# ExtensionConnector.net
KiCad netlist of a schematic drawn in Altium Designer
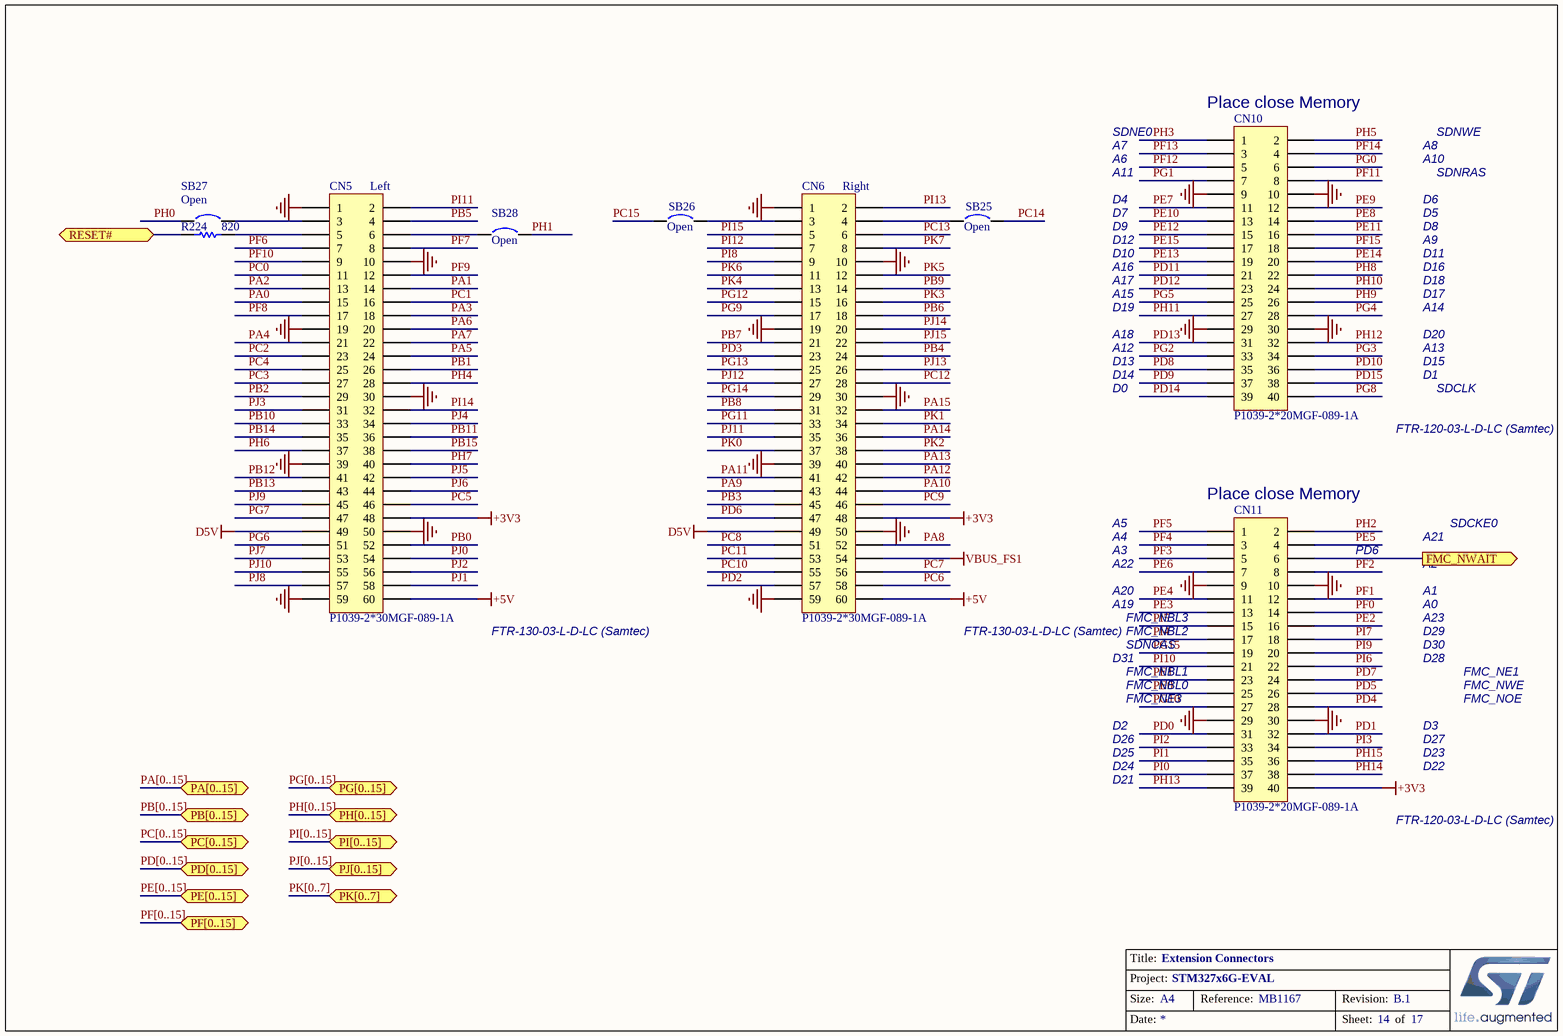
[diagram p0: ExtensionConnector.SchDoc]

(export (version "E")
  (design (tool "Eeschema 10.0.6"))
  (components
    (comp (ref "CN5")
      (value "P1039-2*30MGF-089-1A")
      (footprint "FTR-130-53-L-D-LC")
      (description "Header, 40-Pin, Dual row")
      (fields (field (name "PUBLISHER") "Altium Limited"))
      (libsource (lib "mb1045") (part "FTR-130-53-L-D-LC"))
    )
    (comp (ref "CN6")
      (value "P1039-2*30MGF-089-1A")
      (footprint "FTR-130-53-L-D-LC")
      (description "Header, 40-Pin, Dual row")
      (fields (field (name "PUBLISHER") "Altium Limited"))
      (libsource (lib "mb1045") (part "FTR-130-53-L-D-LC"))
    )
    (comp (ref "CN10")
      (value "P1039-2*20MGF-089-1A")
      (footprint "FTR-120-53-L-D-LC")
      (description "Header, 20-Pin, Dual row")
      (fields (field (name "PUBLISHER") "Altium Limited"))
      (libsource (lib "mb1045") (part "FTR-120-53-L-D-LC"))
    )
    (comp (ref "CN11")
      (value "P1039-2*20MGF-089-1A")
      (footprint "FTR-120-53-L-D-LC")
      (description "Header, 20-Pin, Dual row")
      (fields (field (name "PUBLISHER") "Altium Limited"))
      (libsource (lib "mb1045") (part "FTR-120-53-L-D-LC"))
    )
    (comp (ref "R224")
      (value "820")
      (footprint "0603R")
      (description "Resistor")
      (fields (field (name "PUBLISHER") "Altium Limited"))
      (libsource (lib "Miscellaneous Devices") (part "res1"))
    )
    (comp (ref "SB25")
      (value "Open")
      (footprint "SB_0603")
      (description "Circuit Breaker")
      (fields (field (name "PUBLISHER") "Altium Limited"))
      (libsource (lib "MB1167") (part "Circuit Breaker"))
    )
    (comp (ref "SB26")
      (value "Open")
      (footprint "SB_0603")
      (description "Circuit Breaker")
      (fields (field (name "PUBLISHER") "Altium Limited"))
      (libsource (lib "") (part "Circuit Breaker_1"))
    )
    (comp (ref "SB27")
      (value "Open")
      (footprint "SB_0603")
      (description "Circuit Breaker")
      (fields (field (name "PUBLISHER") "Altium Limited"))
      (libsource (lib "") (part "Circuit Breaker_1"))
    )
    (comp (ref "SB28")
      (value "Open")
      (footprint "SB_0603")
      (description "Circuit Breaker")
      (fields (field (name "PUBLISHER") "Altium Limited"))
      (libsource (lib "MB1167") (part "Circuit Breaker"))
    )
  )
  (nets
    (net (code "1") (name "+3V3") (class "Default")
      (node (ref "CN11") (pin "40") (pinfunction "40_40") (pintype "passive"))
      (node (ref "CN5") (pin "48") (pinfunction "48_48") (pintype "passive"))
      (node (ref "CN6") (pin "48") (pinfunction "48_48") (pintype "passive"))
    )
    (net (code "2") (name "+5V") (class "Default")
      (node (ref "CN5") (pin "60") (pinfunction "60_60") (pintype "passive"))
      (node (ref "CN6") (pin "60") (pinfunction "60_60") (pintype "passive"))
    )
    (net (code "3") (name "/FMC_NWAIT") (class "Default")
      (node (ref "CN11") (pin "6") (pinfunction "6_6") (pintype "passive"))
    )
    (net (code "4") (name "/PA0") (class "Default")
      (node (ref "CN5") (pin "15") (pinfunction "15_15") (pintype "passive"))
    )
    (net (code "5") (name "/PA1") (class "Default")
      (node (ref "CN5") (pin "14") (pinfunction "14_14") (pintype "passive"))
    )
    (net (code "6") (name "/PA2") (class "Default")
      (node (ref "CN5") (pin "13") (pinfunction "13_13") (pintype "passive"))
    )
    (net (code "7") (name "/PA3") (class "Default")
      (node (ref "CN5") (pin "18") (pinfunction "18_18") (pintype "passive"))
    )
    (net (code "8") (name "/PA4") (class "Default")
      (node (ref "CN5") (pin "21") (pinfunction "21_21") (pintype "passive"))
    )
    (net (code "9") (name "/PA5") (class "Default")
      (node (ref "CN5") (pin "24") (pinfunction "24_24") (pintype "passive"))
    )
    (net (code "10") (name "/PA6") (class "Default")
      (node (ref "CN5") (pin "20") (pinfunction "20_20") (pintype "passive"))
    )
    (net (code "11") (name "/PA7") (class "Default")
      (node (ref "CN5") (pin "22") (pinfunction "22_22") (pintype "passive"))
    )
    (net (code "12") (name "/PA8") (class "Default")
      (node (ref "CN6") (pin "52") (pinfunction "52_52") (pintype "passive"))
    )
    (net (code "13") (name "/PA9") (class "Default")
      (node (ref "CN6") (pin "43") (pinfunction "43_43") (pintype "passive"))
    )
    (net (code "14") (name "/PA10") (class "Default")
      (node (ref "CN6") (pin "44") (pinfunction "44_44") (pintype "passive"))
    )
    (net (code "15") (name "/PA11") (class "Default")
      (node (ref "CN6") (pin "41") (pinfunction "41_41") (pintype "passive"))
    )
    (net (code "16") (name "/PA12") (class "Default")
      (node (ref "CN6") (pin "42") (pinfunction "42_42") (pintype "passive"))
    )
    (net (code "17") (name "/PA13") (class "Default")
      (node (ref "CN6") (pin "40") (pinfunction "40_40") (pintype "passive"))
    )
    (net (code "18") (name "/PA14") (class "Default")
      (node (ref "CN6") (pin "36") (pinfunction "36_36") (pintype "passive"))
    )
    (net (code "19") (name "/PA15") (class "Default")
      (node (ref "CN6") (pin "32") (pinfunction "32_32") (pintype "passive"))
    )
    (net (code "21") (name "/PB0") (class "Default")
      (node (ref "CN5") (pin "52") (pinfunction "52_52") (pintype "passive"))
    )
    (net (code "22") (name "/PB1") (class "Default")
      (node (ref "CN5") (pin "26") (pinfunction "26_26") (pintype "passive"))
    )
    (net (code "23") (name "/PB2") (class "Default")
      (node (ref "CN5") (pin "29") (pinfunction "29_29") (pintype "passive"))
    )
    (net (code "24") (name "/PB3") (class "Default")
      (node (ref "CN6") (pin "45") (pinfunction "45_45") (pintype "passive"))
    )
    (net (code "25") (name "/PB4") (class "Default")
      (node (ref "CN6") (pin "24") (pinfunction "24_24") (pintype "passive"))
    )
    (net (code "26") (name "/PB5") (class "Default")
      (node (ref "CN5") (pin "4") (pinfunction "4_4") (pintype "passive"))
    )
    (net (code "27") (name "/PB6") (class "Default")
      (node (ref "CN6") (pin "18") (pinfunction "18_18") (pintype "passive"))
    )
    (net (code "28") (name "/PB7") (class "Default")
      (node (ref "CN6") (pin "21") (pinfunction "21_21") (pintype "passive"))
    )
    (net (code "29") (name "/PB8") (class "Default")
      (node (ref "CN6") (pin "31") (pinfunction "31_31") (pintype "passive"))
    )
    (net (code "30") (name "/PB9") (class "Default")
      (node (ref "CN6") (pin "14") (pinfunction "14_14") (pintype "passive"))
    )
    (net (code "31") (name "/PB10") (class "Default")
      (node (ref "CN5") (pin "33") (pinfunction "33_33") (pintype "passive"))
    )
    (net (code "32") (name "/PB11") (class "Default")
      (node (ref "CN5") (pin "36") (pinfunction "36_36") (pintype "passive"))
    )
    (net (code "33") (name "/PB12") (class "Default")
      (node (ref "CN5") (pin "41") (pinfunction "41_41") (pintype "passive"))
    )
    (net (code "34") (name "/PB13") (class "Default")
      (node (ref "CN5") (pin "43") (pinfunction "43_43") (pintype "passive"))
    )
    (net (code "35") (name "/PB14") (class "Default")
      (node (ref "CN5") (pin "35") (pinfunction "35_35") (pintype "passive"))
    )
    (net (code "36") (name "/PB15") (class "Default")
      (node (ref "CN5") (pin "38") (pinfunction "38_38") (pintype "passive"))
    )
    (net (code "38") (name "/PC0") (class "Default")
      (node (ref "CN5") (pin "11") (pinfunction "11_11") (pintype "passive"))
    )
    (net (code "39") (name "/PC1") (class "Default")
      (node (ref "CN5") (pin "16") (pinfunction "16_16") (pintype "passive"))
    )
    (net (code "40") (name "/PC2") (class "Default")
      (node (ref "CN5") (pin "23") (pinfunction "23_23") (pintype "passive"))
    )
    (net (code "41") (name "/PC3") (class "Default")
      (node (ref "CN5") (pin "27") (pinfunction "27_27") (pintype "passive"))
    )
    (net (code "42") (name "/PC4") (class "Default")
      (node (ref "CN5") (pin "25") (pinfunction "25_25") (pintype "passive"))
    )
    (net (code "43") (name "/PC5") (class "Default")
      (node (ref "CN5") (pin "46") (pinfunction "46_46") (pintype "passive"))
    )
    (net (code "44") (name "/PC6") (class "Default")
      (node (ref "CN6") (pin "58") (pinfunction "58_58") (pintype "passive"))
    )
    (net (code "45") (name "/PC7") (class "Default")
      (node (ref "CN6") (pin "56") (pinfunction "56_56") (pintype "passive"))
    )
    (net (code "46") (name "/PC8") (class "Default")
      (node (ref "CN6") (pin "51") (pinfunction "51_51") (pintype "passive"))
    )
    (net (code "47") (name "/PC9") (class "Default")
      (node (ref "CN6") (pin "46") (pinfunction "46_46") (pintype "passive"))
    )
    (net (code "48") (name "/PC10") (class "Default")
      (node (ref "CN6") (pin "55") (pinfunction "55_55") (pintype "passive"))
    )
    (net (code "49") (name "/PC11") (class "Default")
      (node (ref "CN6") (pin "53") (pinfunction "53_53") (pintype "passive"))
    )
    (net (code "50") (name "/PC12") (class "Default")
      (node (ref "CN6") (pin "28") (pinfunction "28_28") (pintype "passive"))
    )
    (net (code "51") (name "/PC13") (class "Default")
      (node (ref "CN6") (pin "6") (pinfunction "6_6") (pintype "passive"))
    )
    (net (code "52") (name "/PC14") (class "Default")
      (node (ref "SB25") (pin "1") (pinfunction "1_1") (pintype "passive"))
    )
    (net (code "53") (name "/PC15") (class "Default")
      (node (ref "SB26") (pin "1") (pinfunction "1_1") (pintype "passive"))
    )
    (net (code "55") (name "/PD0") (class "Default")
      (node (ref "CN11") (pin "31") (pinfunction "31_31") (pintype "passive"))
    )
    (net (code "56") (name "/PD1") (class "Default")
      (node (ref "CN11") (pin "32") (pinfunction "32_32") (pintype "passive"))
    )
    (net (code "57") (name "/PD2") (class "Default")
      (node (ref "CN6") (pin "57") (pinfunction "57_57") (pintype "passive"))
    )
    (net (code "58") (name "/PD3") (class "Default")
      (node (ref "CN6") (pin "23") (pinfunction "23_23") (pintype "passive"))
    )
    (net (code "59") (name "/PD4") (class "Default")
      (node (ref "CN11") (pin "28") (pinfunction "28_28") (pintype "passive"))
    )
    (net (code "60") (name "/PD5") (class "Default")
      (node (ref "CN11") (pin "26") (pinfunction "26_26") (pintype "passive"))
    )
    (net (code "61") (name "/PD6") (class "Default")
      (node (ref "CN6") (pin "47") (pinfunction "47_47") (pintype "passive"))
    )
    (net (code "62") (name "/PD7") (class "Default")
      (node (ref "CN11") (pin "24") (pinfunction "24_24") (pintype "passive"))
    )
    (net (code "63") (name "/PD8") (class "Default")
      (node (ref "CN10") (pin "35") (pinfunction "35_35") (pintype "passive"))
    )
    (net (code "64") (name "/PD9") (class "Default")
      (node (ref "CN10") (pin "37") (pinfunction "37_37") (pintype "passive"))
    )
    (net (code "65") (name "/PD10") (class "Default")
      (node (ref "CN10") (pin "36") (pinfunction "36_36") (pintype "passive"))
    )
    (net (code "66") (name "/PD11") (class "Default")
      (node (ref "CN10") (pin "21") (pinfunction "21_21") (pintype "passive"))
    )
    (net (code "67") (name "/PD12") (class "Default")
      (node (ref "CN10") (pin "23") (pinfunction "23_23") (pintype "passive"))
    )
    (net (code "68") (name "/PD13") (class "Default")
      (node (ref "CN10") (pin "31") (pinfunction "31_31") (pintype "passive"))
    )
    (net (code "69") (name "/PD14") (class "Default")
      (node (ref "CN10") (pin "39") (pinfunction "39_39") (pintype "passive"))
    )
    (net (code "70") (name "/PD15") (class "Default")
      (node (ref "CN10") (pin "38") (pinfunction "38_38") (pintype "passive"))
    )
    (net (code "72") (name "/PE0") (class "Default")
      (node (ref "CN11") (pin "25") (pinfunction "25_25") (pintype "passive"))
    )
    (net (code "73") (name "/PE1") (class "Default")
      (node (ref "CN11") (pin "23") (pinfunction "23_23") (pintype "passive"))
    )
    (net (code "74") (name "/PE2") (class "Default")
      (node (ref "CN11") (pin "16") (pinfunction "16_16") (pintype "passive"))
    )
    (net (code "75") (name "/PE3") (class "Default")
      (node (ref "CN11") (pin "13") (pinfunction "13_13") (pintype "passive"))
    )
    (net (code "76") (name "/PE4") (class "Default")
      (node (ref "CN11") (pin "11") (pinfunction "11_11") (pintype "passive"))
    )
    (net (code "77") (name "/PE5") (class "Default")
      (node (ref "CN11") (pin "4") (pinfunction "4_4") (pintype "passive"))
    )
    (net (code "78") (name "/PE6") (class "Default")
      (node (ref "CN11") (pin "7") (pinfunction "7_7") (pintype "passive"))
    )
    (net (code "79") (name "/PE7") (class "Default")
      (node (ref "CN10") (pin "11") (pinfunction "11_11") (pintype "passive"))
    )
    (net (code "80") (name "/PE8") (class "Default")
      (node (ref "CN10") (pin "14") (pinfunction "14_14") (pintype "passive"))
    )
    (net (code "81") (name "/PE9") (class "Default")
      (node (ref "CN10") (pin "12") (pinfunction "12_12") (pintype "passive"))
    )
    (net (code "82") (name "/PE10") (class "Default")
      (node (ref "CN10") (pin "13") (pinfunction "13_13") (pintype "passive"))
    )
    (net (code "83") (name "/PE11") (class "Default")
      (node (ref "CN10") (pin "16") (pinfunction "16_16") (pintype "passive"))
    )
    (net (code "84") (name "/PE12") (class "Default")
      (node (ref "CN10") (pin "15") (pinfunction "15_15") (pintype "passive"))
    )
    (net (code "85") (name "/PE13") (class "Default")
      (node (ref "CN10") (pin "19") (pinfunction "19_19") (pintype "passive"))
    )
    (net (code "86") (name "/PE14") (class "Default")
      (node (ref "CN10") (pin "20") (pinfunction "20_20") (pintype "passive"))
    )
    (net (code "87") (name "/PE15") (class "Default")
      (node (ref "CN10") (pin "17") (pinfunction "17_17") (pintype "passive"))
    )
    (net (code "89") (name "/PF0") (class "Default")
      (node (ref "CN11") (pin "14") (pinfunction "14_14") (pintype "passive"))
    )
    (net (code "90") (name "/PF1") (class "Default")
      (node (ref "CN11") (pin "12") (pinfunction "12_12") (pintype "passive"))
    )
    (net (code "91") (name "/PF2") (class "Default")
      (node (ref "CN11") (pin "8") (pinfunction "8_8") (pintype "passive"))
    )
    (net (code "92") (name "/PF3") (class "Default")
      (node (ref "CN11") (pin "5") (pinfunction "5_5") (pintype "passive"))
    )
    (net (code "93") (name "/PF4") (class "Default")
      (node (ref "CN11") (pin "3") (pinfunction "3_3") (pintype "passive"))
    )
    (net (code "94") (name "/PF5") (class "Default")
      (node (ref "CN11") (pin "1") (pinfunction "1_1") (pintype "passive"))
    )
    (net (code "95") (name "/PF6") (class "Default")
      (node (ref "CN5") (pin "7") (pinfunction "7_7") (pintype "passive"))
    )
    (net (code "96") (name "/PF7") (class "Default")
      (node (ref "CN5") (pin "8") (pinfunction "8_8") (pintype "passive"))
    )
    (net (code "97") (name "/PF8") (class "Default")
      (node (ref "CN5") (pin "17") (pinfunction "17_17") (pintype "passive"))
    )
    (net (code "98") (name "/PF9") (class "Default")
      (node (ref "CN5") (pin "12") (pinfunction "12_12") (pintype "passive"))
    )
    (net (code "99") (name "/PF10") (class "Default")
      (node (ref "CN5") (pin "9") (pinfunction "9_9") (pintype "passive"))
    )
    (net (code "100") (name "/PF11") (class "Default")
      (node (ref "CN10") (pin "8") (pinfunction "8_8") (pintype "passive"))
    )
    (net (code "101") (name "/PF12") (class "Default")
      (node (ref "CN10") (pin "5") (pinfunction "5_5") (pintype "passive"))
    )
    (net (code "102") (name "/PF13") (class "Default")
      (node (ref "CN10") (pin "3") (pinfunction "3_3") (pintype "passive"))
    )
    (net (code "103") (name "/PF14") (class "Default")
      (node (ref "CN10") (pin "4") (pinfunction "4_4") (pintype "passive"))
    )
    (net (code "104") (name "/PF15") (class "Default")
      (node (ref "CN10") (pin "18") (pinfunction "18_18") (pintype "passive"))
    )
    (net (code "106") (name "/PG0") (class "Default")
      (node (ref "CN10") (pin "6") (pinfunction "6_6") (pintype "passive"))
    )
    (net (code "107") (name "/PG1") (class "Default")
      (node (ref "CN10") (pin "7") (pinfunction "7_7") (pintype "passive"))
    )
    (net (code "108") (name "/PG2") (class "Default")
      (node (ref "CN10") (pin "33") (pinfunction "33_33") (pintype "passive"))
    )
    (net (code "109") (name "/PG3") (class "Default")
      (node (ref "CN10") (pin "34") (pinfunction "34_34") (pintype "passive"))
    )
    (net (code "110") (name "/PG4") (class "Default")
      (node (ref "CN10") (pin "28") (pinfunction "28_28") (pintype "passive"))
    )
    (net (code "111") (name "/PG5") (class "Default")
      (node (ref "CN10") (pin "25") (pinfunction "25_25") (pintype "passive"))
    )
    (net (code "112") (name "/PG6") (class "Default")
      (node (ref "CN5") (pin "51") (pinfunction "51_51") (pintype "passive"))
    )
    (net (code "113") (name "/PG7") (class "Default")
      (node (ref "CN5") (pin "47") (pinfunction "47_47") (pintype "passive"))
    )
    (net (code "114") (name "/PG8") (class "Default")
      (node (ref "CN10") (pin "40") (pinfunction "40_40") (pintype "passive"))
    )
    (net (code "115") (name "/PG9") (class "Default")
      (node (ref "CN6") (pin "17") (pinfunction "17_17") (pintype "passive"))
    )
    (net (code "116") (name "/PG10") (class "Default")
      (node (ref "CN11") (pin "27") (pinfunction "27_27") (pintype "passive"))
    )
    (net (code "117") (name "/PG11") (class "Default")
      (node (ref "CN6") (pin "33") (pinfunction "33_33") (pintype "passive"))
    )
    (net (code "118") (name "/PG12") (class "Default")
      (node (ref "CN6") (pin "15") (pinfunction "15_15") (pintype "passive"))
    )
    (net (code "119") (name "/PG13") (class "Default")
      (node (ref "CN6") (pin "25") (pinfunction "25_25") (pintype "passive"))
    )
    (net (code "120") (name "/PG14") (class "Default")
      (node (ref "CN6") (pin "29") (pinfunction "29_29") (pintype "passive"))
    )
    (net (code "121") (name "/PG15") (class "Default")
      (node (ref "CN11") (pin "19") (pinfunction "19_19") (pintype "passive"))
    )
    (net (code "123") (name "/PH0") (class "Default")
      (node (ref "SB27") (pin "1") (pinfunction "1_1") (pintype "passive"))
    )
    (net (code "124") (name "/PH1") (class "Default")
      (node (ref "SB28") (pin "1") (pinfunction "1_1") (pintype "passive"))
    )
    (net (code "125") (name "/PH2") (class "Default")
      (node (ref "CN11") (pin "2") (pinfunction "2_2") (pintype "passive"))
    )
    (net (code "126") (name "/PH3") (class "Default")
      (node (ref "CN10") (pin "1") (pinfunction "1_1") (pintype "passive"))
    )
    (net (code "127") (name "/PH4") (class "Default")
      (node (ref "CN5") (pin "28") (pinfunction "28_28") (pintype "passive"))
    )
    (net (code "128") (name "/PH5") (class "Default")
      (node (ref "CN10") (pin "2") (pinfunction "2_2") (pintype "passive"))
    )
    (net (code "129") (name "/PH6") (class "Default")
      (node (ref "CN5") (pin "37") (pinfunction "37_37") (pintype "passive"))
    )
    (net (code "130") (name "/PH7") (class "Default")
      (node (ref "CN5") (pin "40") (pinfunction "40_40") (pintype "passive"))
    )
    (net (code "131") (name "/PH8") (class "Default")
      (node (ref "CN10") (pin "22") (pinfunction "22_22") (pintype "passive"))
    )
    (net (code "132") (name "/PH9") (class "Default")
      (node (ref "CN10") (pin "26") (pinfunction "26_26") (pintype "passive"))
    )
    (net (code "133") (name "/PH10") (class "Default")
      (node (ref "CN10") (pin "24") (pinfunction "24_24") (pintype "passive"))
    )
    (net (code "134") (name "/PH11") (class "Default")
      (node (ref "CN10") (pin "27") (pinfunction "27_27") (pintype "passive"))
    )
    (net (code "135") (name "/PH12") (class "Default")
      (node (ref "CN10") (pin "32") (pinfunction "32_32") (pintype "passive"))
    )
    (net (code "136") (name "/PH13") (class "Default")
      (node (ref "CN11") (pin "39") (pinfunction "39_39") (pintype "passive"))
    )
    (net (code "137") (name "/PH14") (class "Default")
      (node (ref "CN11") (pin "38") (pinfunction "38_38") (pintype "passive"))
    )
    (net (code "138") (name "/PH15") (class "Default")
      (node (ref "CN11") (pin "36") (pinfunction "36_36") (pintype "passive"))
    )
    (net (code "140") (name "/PI0") (class "Default")
      (node (ref "CN11") (pin "37") (pinfunction "37_37") (pintype "passive"))
    )
    (net (code "141") (name "/PI1") (class "Default")
      (node (ref "CN11") (pin "35") (pinfunction "35_35") (pintype "passive"))
    )
    (net (code "142") (name "/PI2") (class "Default")
      (node (ref "CN11") (pin "33") (pinfunction "33_33") (pintype "passive"))
    )
    (net (code "143") (name "/PI3") (class "Default")
      (node (ref "CN11") (pin "34") (pinfunction "34_34") (pintype "passive"))
    )
    (net (code "144") (name "/PI4") (class "Default")
      (node (ref "CN11") (pin "17") (pinfunction "17_17") (pintype "passive"))
    )
    (net (code "145") (name "/PI5") (class "Default")
      (node (ref "CN11") (pin "15") (pinfunction "15_15") (pintype "passive"))
    )
    (net (code "146") (name "/PI6") (class "Default")
      (node (ref "CN11") (pin "22") (pinfunction "22_22") (pintype "passive"))
    )
    (net (code "147") (name "/PI7") (class "Default")
      (node (ref "CN11") (pin "18") (pinfunction "18_18") (pintype "passive"))
    )
    (net (code "148") (name "/PI8") (class "Default")
      (node (ref "CN6") (pin "9") (pinfunction "9_9") (pintype "passive"))
    )
    (net (code "149") (name "/PI9") (class "Default")
      (node (ref "CN11") (pin "20") (pinfunction "20_20") (pintype "passive"))
    )
    (net (code "150") (name "/PI10") (class "Default")
      (node (ref "CN11") (pin "21") (pinfunction "21_21") (pintype "passive"))
    )
    (net (code "151") (name "/PI11") (class "Default")
      (node (ref "CN5") (pin "2") (pinfunction "2_2") (pintype "passive"))
    )
    (net (code "152") (name "/PI12") (class "Default")
      (node (ref "CN6") (pin "7") (pinfunction "7_7") (pintype "passive"))
    )
    (net (code "153") (name "/PI13") (class "Default")
      (node (ref "CN6") (pin "2") (pinfunction "2_2") (pintype "passive"))
    )
    (net (code "154") (name "/PI14") (class "Default")
      (node (ref "CN5") (pin "32") (pinfunction "32_32") (pintype "passive"))
    )
    (net (code "155") (name "/PI15") (class "Default")
      (node (ref "CN6") (pin "5") (pinfunction "5_5") (pintype "passive"))
    )
    (net (code "157") (name "/PJ0") (class "Default")
      (node (ref "CN5") (pin "54") (pinfunction "54_54") (pintype "passive"))
    )
    (net (code "158") (name "/PJ1") (class "Default")
      (node (ref "CN5") (pin "58") (pinfunction "58_58") (pintype "passive"))
    )
    (net (code "159") (name "/PJ2") (class "Default")
      (node (ref "CN5") (pin "56") (pinfunction "56_56") (pintype "passive"))
    )
    (net (code "160") (name "/PJ3") (class "Default")
      (node (ref "CN5") (pin "31") (pinfunction "31_31") (pintype "passive"))
    )
    (net (code "161") (name "/PJ4") (class "Default")
      (node (ref "CN5") (pin "34") (pinfunction "34_34") (pintype "passive"))
    )
    (net (code "162") (name "/PJ5") (class "Default")
      (node (ref "CN5") (pin "42") (pinfunction "42_42") (pintype "passive"))
    )
    (net (code "163") (name "/PJ6") (class "Default")
      (node (ref "CN5") (pin "44") (pinfunction "44_44") (pintype "passive"))
    )
    (net (code "164") (name "/PJ7") (class "Default")
      (node (ref "CN5") (pin "53") (pinfunction "53_53") (pintype "passive"))
    )
    (net (code "165") (name "/PJ8") (class "Default")
      (node (ref "CN5") (pin "57") (pinfunction "57_57") (pintype "passive"))
    )
    (net (code "166") (name "/PJ9") (class "Default")
      (node (ref "CN5") (pin "45") (pinfunction "45_45") (pintype "passive"))
    )
    (net (code "167") (name "/PJ10") (class "Default")
      (node (ref "CN5") (pin "55") (pinfunction "55_55") (pintype "passive"))
    )
    (net (code "168") (name "/PJ11") (class "Default")
      (node (ref "CN6") (pin "35") (pinfunction "35_35") (pintype "passive"))
    )
    (net (code "169") (name "/PJ12") (class "Default")
      (node (ref "CN6") (pin "27") (pinfunction "27_27") (pintype "passive"))
    )
    (net (code "170") (name "/PJ13") (class "Default")
      (node (ref "CN6") (pin "26") (pinfunction "26_26") (pintype "passive"))
    )
    (net (code "171") (name "/PJ14") (class "Default")
      (node (ref "CN6") (pin "20") (pinfunction "20_20") (pintype "passive"))
    )
    (net (code "172") (name "/PJ15") (class "Default")
      (node (ref "CN6") (pin "22") (pinfunction "22_22") (pintype "passive"))
    )
    (net (code "174") (name "/PK0") (class "Default")
      (node (ref "CN6") (pin "37") (pinfunction "37_37") (pintype "passive"))
    )
    (net (code "175") (name "/PK1") (class "Default")
      (node (ref "CN6") (pin "34") (pinfunction "34_34") (pintype "passive"))
    )
    (net (code "176") (name "/PK2") (class "Default")
      (node (ref "CN6") (pin "38") (pinfunction "38_38") (pintype "passive"))
    )
    (net (code "177") (name "/PK3") (class "Default")
      (node (ref "CN6") (pin "16") (pinfunction "16_16") (pintype "passive"))
    )
    (net (code "178") (name "/PK4") (class "Default")
      (node (ref "CN6") (pin "13") (pinfunction "13_13") (pintype "passive"))
    )
    (net (code "179") (name "/PK5") (class "Default")
      (node (ref "CN6") (pin "12") (pinfunction "12_12") (pintype "passive"))
    )
    (net (code "180") (name "/PK6") (class "Default")
      (node (ref "CN6") (pin "11") (pinfunction "11_11") (pintype "passive"))
    )
    (net (code "181") (name "/PK7") (class "Default")
      (node (ref "CN6") (pin "8") (pinfunction "8_8") (pintype "passive"))
    )
    (net (code "183") (name "/RESET#") (class "Default")
      (node (ref "R224") (pin "1") (pinfunction "1_1") (pintype "passive"))
    )
    (net (code "184") (name "D5V") (class "Default")
      (node (ref "CN5") (pin "49") (pinfunction "49_49") (pintype "passive"))
      (node (ref "CN6") (pin "49") (pinfunction "49_49") (pintype "passive"))
    )
    (net (code "185") (name "GND") (class "Default")
      (node (ref "CN10") (pin "10") (pinfunction "10_10") (pintype "passive"))
      (node (ref "CN10") (pin "29") (pinfunction "29_29") (pintype "passive"))
      (node (ref "CN10") (pin "30") (pinfunction "30_30") (pintype "passive"))
      (node (ref "CN10") (pin "9") (pinfunction "9_9") (pintype "passive"))
      (node (ref "CN11") (pin "10") (pinfunction "10_10") (pintype "passive"))
      (node (ref "CN11") (pin "29") (pinfunction "29_29") (pintype "passive"))
      (node (ref "CN11") (pin "30") (pinfunction "30_30") (pintype "passive"))
      (node (ref "CN11") (pin "9") (pinfunction "9_9") (pintype "passive"))
      (node (ref "CN5") (pin "1") (pinfunction "1_1") (pintype "passive"))
      (node (ref "CN5") (pin "10") (pinfunction "10_10") (pintype "passive"))
      (node (ref "CN5") (pin "19") (pinfunction "19_19") (pintype "passive"))
      (node (ref "CN5") (pin "30") (pinfunction "30_30") (pintype "passive"))
      (node (ref "CN5") (pin "39") (pinfunction "39_39") (pintype "passive"))
      (node (ref "CN5") (pin "50") (pinfunction "50_50") (pintype "passive"))
      (node (ref "CN5") (pin "59") (pinfunction "59_59") (pintype "passive"))
      (node (ref "CN6") (pin "1") (pinfunction "1_1") (pintype "passive"))
      (node (ref "CN6") (pin "10") (pinfunction "10_10") (pintype "passive"))
      (node (ref "CN6") (pin "19") (pinfunction "19_19") (pintype "passive"))
      (node (ref "CN6") (pin "30") (pinfunction "30_30") (pintype "passive"))
      (node (ref "CN6") (pin "39") (pinfunction "39_39") (pintype "passive"))
      (node (ref "CN6") (pin "50") (pinfunction "50_50") (pintype "passive"))
      (node (ref "CN6") (pin "59") (pinfunction "59_59") (pintype "passive"))
    )
    (net (code "186") (name "Net-(CN5-Pad3)") (class "Default")
      (node (ref "CN5") (pin "3") (pinfunction "3_3") (pintype "passive"))
      (node (ref "SB27") (pin "2") (pinfunction "2_2") (pintype "passive"))
    )
    (net (code "187") (name "Net-(CN5-Pad5)") (class "Default")
      (node (ref "CN5") (pin "5") (pinfunction "5_5") (pintype "passive"))
      (node (ref "R224") (pin "2") (pinfunction "2_2") (pintype "passive"))
    )
    (net (code "188") (name "Net-(CN5-Pad6)") (class "Default")
      (node (ref "CN5") (pin "6") (pinfunction "6_6") (pintype "passive"))
      (node (ref "SB28") (pin "2") (pinfunction "2_2") (pintype "passive"))
    )
    (net (code "189") (name "Net-(CN6-Pad3)") (class "Default")
      (node (ref "CN6") (pin "3") (pinfunction "3_3") (pintype "passive"))
      (node (ref "SB26") (pin "2") (pinfunction "2_2") (pintype "passive"))
    )
    (net (code "190") (name "Net-(CN6-Pad4)") (class "Default")
      (node (ref "CN6") (pin "4") (pinfunction "4_4") (pintype "passive"))
      (node (ref "SB25") (pin "2") (pinfunction "2_2") (pintype "passive"))
    )
    (net (code "191") (name "VBUS_FS1") (class "Default")
      (node (ref "CN6") (pin "54") (pinfunction "54_54") (pintype "passive"))
    )
  )
)
